# V4.net
KiCad netlist of a schematic drawn in Altium Designer
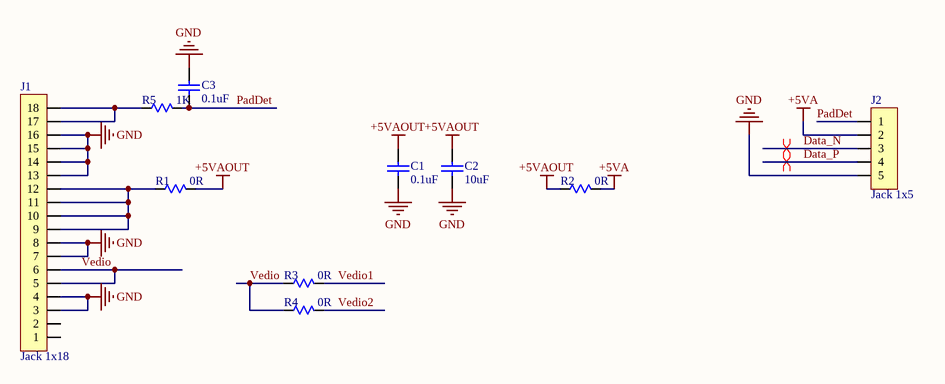
[diagram p0: 海关全向控制器视频采集卡转接板V4.SchDoc]

(export (version "E")
  (design (tool "Eeschema 10.0.6"))
  (components
    (comp (ref "C1") (value "0.1uF") (footprint "C0805") (libsource (lib "SMD") (part "Cap Semi")))
    (comp (ref "C2") (value "10uF") (footprint "C0805") (libsource (lib "SMD") (part "Cap Semi")))
    (comp (ref "C3") (value "0.1uF") (footprint "C0805") (libsource (lib "SMD") (part "Cap Semi")))
    (comp (ref "J1")
      (value "Jack 1x18")
      (footprint "0.5S-6X-18PB")
      (description "插座")
      (libsource (lib "Connector") (part "Jack 1x18"))
    )
    (comp (ref "J2")
      (value "Jack 1x5")
      (footprint "35363-0560")
      (description "插座")
      (libsource (lib "Connector") (part "Jack 1x5"))
    )
    (comp (ref "R1")
      (value "0R")
      (footprint "R0805")
      (description "Resistor")
      (fields (field (name "PUBLISHER") "Altium Limited"))
      (libsource (lib "UP-Robot") (part "Res"))
    )
    (comp (ref "R2")
      (value "0R")
      (footprint "R0805")
      (description "Resistor")
      (fields (field (name "PUBLISHER") "Altium Limited"))
      (libsource (lib "UP-Robot") (part "Res"))
    )
    (comp (ref "R3")
      (value "0R")
      (footprint "R0805")
      (description "Resistor")
      (fields (field (name "PUBLISHER") "Altium Limited"))
      (libsource (lib "UP-Robot") (part "Res"))
    )
    (comp (ref "R4")
      (value "0R")
      (footprint "R0805")
      (description "Resistor")
      (fields (field (name "PUBLISHER") "Altium Limited"))
      (libsource (lib "UP-Robot") (part "Res"))
    )
    (comp (ref "R5")
      (value "1K")
      (footprint "R0805")
      (description "Resistor")
      (fields (field (name "PUBLISHER") "Altium Limited"))
      (libsource (lib "UP-Robot") (part "Res"))
    )
  )
  (nets
    (net (code "1") (name "+5VA") (class "Default")
      (node (ref "J2") (pin "2") (pinfunction "2_2") (pintype "passive"))
      (node (ref "R2") (pin "2") (pinfunction "2_2") (pintype "passive"))
    )
    (net (code "2") (name "+5VAOUT") (class "Default")
      (node (ref "C1") (pin "2") (pinfunction "2_2") (pintype "passive"))
      (node (ref "C2") (pin "2") (pinfunction "2_2") (pintype "passive"))
      (node (ref "R1") (pin "2") (pinfunction "2_2") (pintype "passive"))
      (node (ref "R2") (pin "1") (pinfunction "1_1") (pintype "passive"))
    )
    (net (code "3") (name "/Data_N") (class "Default")
      (node (ref "J2") (pin "3") (pinfunction "3_3") (pintype "passive"))
    )
    (net (code "4") (name "/Data_P") (class "Default")
      (node (ref "J2") (pin "4") (pinfunction "4_4") (pintype "passive"))
    )
    (net (code "5") (name "/PadDet") (class "Default")
      (node (ref "C3") (pin "1") (pinfunction "1_1") (pintype "passive"))
      (node (ref "J2") (pin "1") (pinfunction "1_1") (pintype "passive"))
      (node (ref "R5") (pin "2") (pinfunction "2_2") (pintype "passive"))
    )
    (net (code "6") (name "/Vedio") (class "Default")
      (node (ref "J1") (pin "5") (pinfunction "5_5") (pintype "passive"))
      (node (ref "J1") (pin "6") (pinfunction "6_6") (pintype "passive"))
      (node (ref "R3") (pin "1") (pinfunction "1_1") (pintype "passive"))
      (node (ref "R4") (pin "1") (pinfunction "1_1") (pintype "passive"))
    )
    (net (code "7") (name "/Vedio1") (class "Default")
      (node (ref "R3") (pin "2") (pinfunction "2_2") (pintype "passive"))
    )
    (net (code "8") (name "/Vedio2") (class "Default")
      (node (ref "R4") (pin "2") (pinfunction "2_2") (pintype "passive"))
    )
    (net (code "9") (name "GND") (class "Default")
      (node (ref "C1") (pin "1") (pinfunction "1_1") (pintype "passive"))
      (node (ref "C2") (pin "1") (pinfunction "1_1") (pintype "passive"))
      (node (ref "C3") (pin "2") (pinfunction "2_2") (pintype "passive"))
      (node (ref "J1") (pin "13") (pinfunction "13_13") (pintype "passive"))
      (node (ref "J1") (pin "14") (pinfunction "14_14") (pintype "passive"))
      (node (ref "J1") (pin "15") (pinfunction "15_15") (pintype "passive"))
      (node (ref "J1") (pin "16") (pinfunction "16_16") (pintype "passive"))
      (node (ref "J1") (pin "3") (pinfunction "3_3") (pintype "passive"))
      (node (ref "J1") (pin "4") (pinfunction "4_4") (pintype "passive"))
      (node (ref "J1") (pin "7") (pinfunction "7_7") (pintype "passive"))
      (node (ref "J1") (pin "8") (pinfunction "8_8") (pintype "passive"))
      (node (ref "J2") (pin "5") (pinfunction "5_5") (pintype "passive"))
    )
    (net (code "10") (name "Net-(J1-Pad10)") (class "Default")
      (node (ref "J1") (pin "10") (pinfunction "10_10") (pintype "passive"))
      (node (ref "J1") (pin "11") (pinfunction "11_11") (pintype "passive"))
      (node (ref "J1") (pin "12") (pinfunction "12_12") (pintype "passive"))
      (node (ref "J1") (pin "9") (pinfunction "9_9") (pintype "passive"))
      (node (ref "R1") (pin "1") (pinfunction "1_1") (pintype "passive"))
    )
    (net (code "11") (name "Net-(J1-Pad17)") (class "Default")
      (node (ref "J1") (pin "17") (pinfunction "17_17") (pintype "passive"))
      (node (ref "J1") (pin "18") (pinfunction "18_18") (pintype "passive"))
      (node (ref "R5") (pin "1") (pinfunction "1_1") (pintype "passive"))
    )
    (net (code "12") (name "unconnected-(J1-Pad1)") (class "Default")
      (node (ref "J1") (pin "1") (pinfunction "1_1") (pintype "passive"))
    )
    (net (code "13") (name "unconnected-(J1-Pad2)") (class "Default")
      (node (ref "J1") (pin "2") (pinfunction "2_2") (pintype "passive"))
    )
  )
)
